# Master_MicroController_LED.net
KiCad netlist of a schematic drawn in Altium Designer
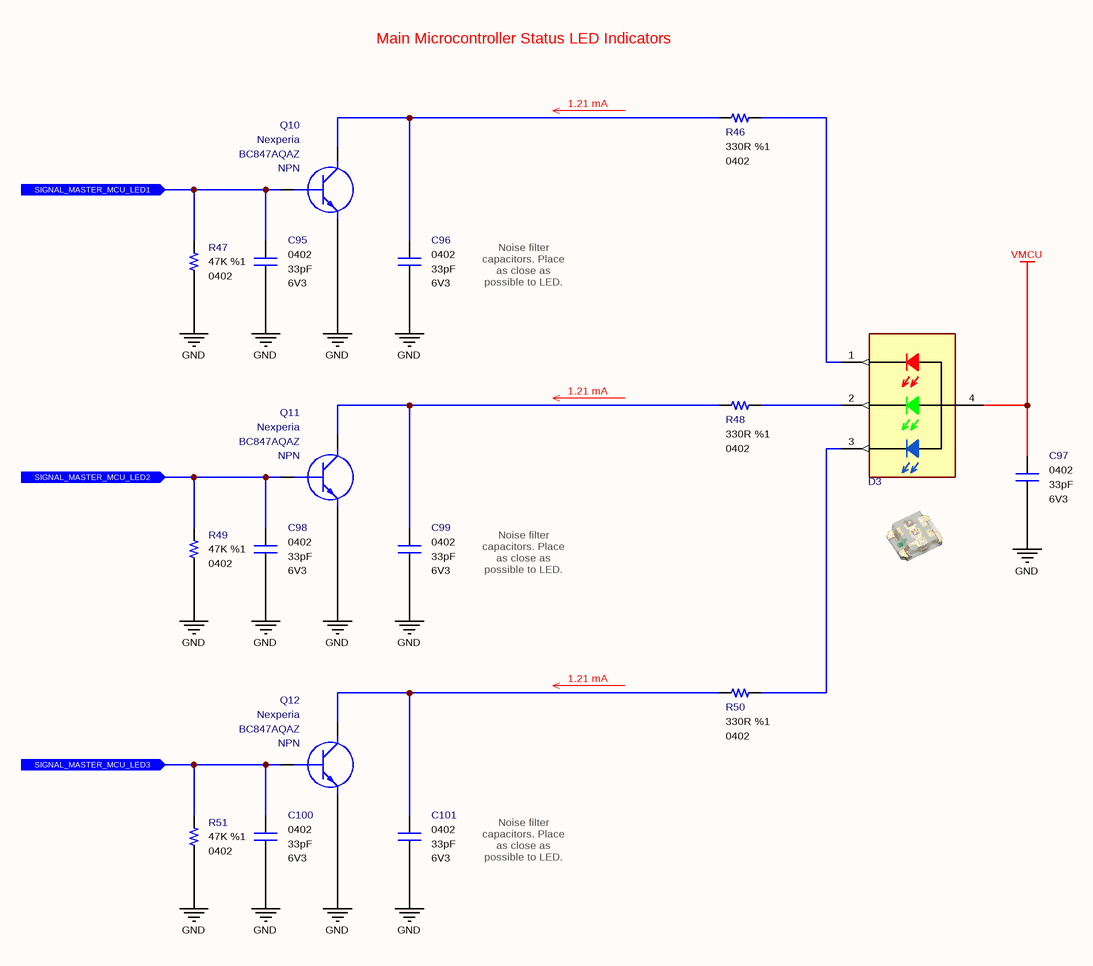
[diagram p0: Master MicroController LED.SchDoc]

(export (version "E")
  (design (tool "Eeschema 10.0.6"))
  (components
    (comp (ref "C95")
      (value "33pF")
      (footprint "CAPACITOR_0402")
      (description "Capacitor - 33pF [0402] (Ceramic)")
      (fields
        (field (name "CASE") "0402")
        (field (name "TOLERANCE") "10%")
        (field (name "VOLTAGE") "6V3")
        (field (name "MANUFACTURER PART NUMBER") "C0402C330J9RACAUTO")
      )
      (libsource (lib "Ovoo_Library") (part "Capacitor - 33pF [0402-6V3]"))
    )
    (comp (ref "C96")
      (value "33pF")
      (footprint "CAPACITOR_0402")
      (description "Capacitor - 33pF [0402] (Ceramic)")
      (fields
        (field (name "CASE") "0402")
        (field (name "TOLERANCE") "10%")
        (field (name "VOLTAGE") "6V3")
        (field (name "MANUFACTURER PART NUMBER") "C0402C330J9RACAUTO")
      )
      (libsource (lib "Ovoo_Library") (part "Capacitor - 33pF [0402-6V3]"))
    )
    (comp (ref "C97")
      (value "33pF")
      (footprint "CAPACITOR_0402")
      (description "Capacitor - 33pF [0402] (Ceramic)")
      (fields
        (field (name "CASE") "0402")
        (field (name "TOLERANCE") "10%")
        (field (name "VOLTAGE") "6V3")
        (field (name "MANUFACTURER PART NUMBER") "C0402C330J9RACAUTO")
      )
      (libsource (lib "Ovoo_Library") (part "Capacitor - 33pF [0402-6V3]"))
    )
    (comp (ref "C98")
      (value "33pF")
      (footprint "CAPACITOR_0402")
      (description "Capacitor - 33pF [0402] (Ceramic)")
      (fields
        (field (name "CASE") "0402")
        (field (name "TOLERANCE") "10%")
        (field (name "VOLTAGE") "6V3")
        (field (name "MANUFACTURER PART NUMBER") "C0402C330J9RACAUTO")
      )
      (libsource (lib "Ovoo_Library") (part "Capacitor - 33pF [0402-6V3]"))
    )
    (comp (ref "C99")
      (value "33pF")
      (footprint "CAPACITOR_0402")
      (description "Capacitor - 33pF [0402] (Ceramic)")
      (fields
        (field (name "CASE") "0402")
        (field (name "TOLERANCE") "10%")
        (field (name "VOLTAGE") "6V3")
        (field (name "MANUFACTURER PART NUMBER") "C0402C330J9RACAUTO")
      )
      (libsource (lib "Ovoo_Library") (part "Capacitor - 33pF [0402-6V3]"))
    )
    (comp (ref "C100")
      (value "33pF")
      (footprint "CAPACITOR_0402")
      (description "Capacitor - 33pF [0402] (Ceramic)")
      (fields
        (field (name "CASE") "0402")
        (field (name "TOLERANCE") "10%")
        (field (name "VOLTAGE") "6V3")
        (field (name "MANUFACTURER PART NUMBER") "C0402C330J9RACAUTO")
      )
      (libsource (lib "Ovoo_Library") (part "Capacitor - 33pF [0402-6V3]"))
    )
    (comp (ref "C101")
      (value "33pF")
      (footprint "CAPACITOR_0402")
      (description "Capacitor - 33pF [0402] (Ceramic)")
      (fields
        (field (name "CASE") "0402")
        (field (name "TOLERANCE") "10%")
        (field (name "VOLTAGE") "6V3")
        (field (name "MANUFACTURER PART NUMBER") "C0402C330J9RACAUTO")
      )
      (libsource (lib "Ovoo_Library") (part "Capacitor - 33pF [0402-6V3]"))
    )
    (comp (ref "D3")
      (value "150066M153000")
      (footprint "Wurth_0606")
      (description "Standard LEDs - SMD PICOLED series Red LED")
      (fields (field (name "MOUSER PART NUMBER") "710-150066M153000"))
      (libsource (lib "Ovoo_Library") (part "Diode - RGB LED (150066M153000)"))
    )
    (comp (ref "Q10")
      (value "Bipolar NPN Transistors")
      (footprint "SOT1215")
      (description "Bipolar Transistors - BJT BC847AQA/DFN1010D-3/REEL 7\" Q2")
      (fields
        (field (name "MOUSER_PART_NUMBER") "771-BC847AQAZ")
        (field (name "MANUFACTURER_NAME") "Nexperia")
        (field (name "MANUFACTURER_PART_NUMBER") "BC847AQAZ")
        (field (name "POLARITY") "NPN")
      )
      (libsource (lib "Ovoo_Library") (part "Transistor - BC847"))
    )
    (comp (ref "Q11")
      (value "Bipolar NPN Transistors")
      (footprint "SOT1215")
      (description "Bipolar Transistors - BJT BC847AQA/DFN1010D-3/REEL 7\" Q2")
      (fields
        (field (name "MOUSER_PART_NUMBER") "771-BC847AQAZ")
        (field (name "MANUFACTURER_NAME") "Nexperia")
        (field (name "MANUFACTURER_PART_NUMBER") "BC847AQAZ")
        (field (name "POLARITY") "NPN")
      )
      (libsource (lib "Ovoo_Library") (part "Transistor - BC847"))
    )
    (comp (ref "Q12")
      (value "Bipolar NPN Transistors")
      (footprint "SOT1215")
      (description "Bipolar Transistors - BJT BC847AQA/DFN1010D-3/REEL 7\" Q2")
      (fields
        (field (name "MOUSER_PART_NUMBER") "771-BC847AQAZ")
        (field (name "MANUFACTURER_NAME") "Nexperia")
        (field (name "MANUFACTURER_PART_NUMBER") "BC847AQAZ")
        (field (name "POLARITY") "NPN")
      )
      (libsource (lib "Ovoo_Library") (part "Transistor - BC847"))
    )
    (comp (ref "R46")
      (value "330R")
      (footprint "RESISTOR_0402")
      (description "Thick Film Resistors - SMD 1/16 W 330 Ohm 1%")
      (fields
        (field (name "TOLERANCE") "%1")
        (field (name "CASE") "0402")
        (field (name "MANUFACTURER PART NUMBER") "CRCW0402330RFKED")
        (field (name "MOUSER PART NUMBER") "71-CRCW0402-330-E3")
      )
      (libsource (lib "Ovoo_Library") (part "Resistor - 330R"))
    )
    (comp (ref "R47")
      (value "47K")
      (footprint "RESISTOR_0402")
      (description "Thick Film Resistors - SMD 1/16 W 47 Kohms 1%")
      (fields
        (field (name "TOLERANCE") "%1")
        (field (name "CASE") "0402")
        (field (name "MANUFACTURER PART NUMBER") "CRCW040247K0FKED")
        (field (name "MOUSER PART NUMBER") "71-CRCW0402-47K-E3")
      )
      (libsource (lib "Ovoo_Library") (part "Resistor - 47K"))
    )
    (comp (ref "R48")
      (value "330R")
      (footprint "RESISTOR_0402")
      (description "Thick Film Resistors - SMD 1/16 W 330 Ohm 1%")
      (fields
        (field (name "TOLERANCE") "%1")
        (field (name "CASE") "0402")
        (field (name "MANUFACTURER PART NUMBER") "CRCW0402330RFKED")
        (field (name "MOUSER PART NUMBER") "71-CRCW0402-330-E3")
      )
      (libsource (lib "Ovoo_Library") (part "Resistor - 330R"))
    )
    (comp (ref "R49")
      (value "47K")
      (footprint "RESISTOR_0402")
      (description "Thick Film Resistors - SMD 1/16 W 47 Kohms 1%")
      (fields
        (field (name "TOLERANCE") "%1")
        (field (name "CASE") "0402")
        (field (name "MANUFACTURER PART NUMBER") "CRCW040247K0FKED")
        (field (name "MOUSER PART NUMBER") "71-CRCW0402-47K-E3")
      )
      (libsource (lib "Ovoo_Library") (part "Resistor - 47K"))
    )
    (comp (ref "R50")
      (value "330R")
      (footprint "RESISTOR_0402")
      (description "Thick Film Resistors - SMD 1/16 W 330 Ohm 1%")
      (fields
        (field (name "TOLERANCE") "%1")
        (field (name "CASE") "0402")
        (field (name "MANUFACTURER PART NUMBER") "CRCW0402330RFKED")
        (field (name "MOUSER PART NUMBER") "71-CRCW0402-330-E3")
      )
      (libsource (lib "Ovoo_Library") (part "Resistor - 330R"))
    )
    (comp (ref "R51")
      (value "47K")
      (footprint "RESISTOR_0402")
      (description "Thick Film Resistors - SMD 1/16 W 47 Kohms 1%")
      (fields
        (field (name "TOLERANCE") "%1")
        (field (name "CASE") "0402")
        (field (name "MANUFACTURER PART NUMBER") "CRCW040247K0FKED")
        (field (name "MOUSER PART NUMBER") "71-CRCW0402-47K-E3")
      )
      (libsource (lib "Ovoo_Library") (part "Resistor - 47K"))
    )
  )
  (nets
    (net (code "1") (name "/SIGNAL_MASTER_MCU_LED1") (class "Default")
      (node (ref "C95") (pin "1") (pinfunction "1_1") (pintype "passive"))
      (node (ref "Q10") (pin "1") (pinfunction "B_1") (pintype "passive"))
      (node (ref "R47") (pin "2") (pinfunction "2_2") (pintype "passive"))
    )
    (net (code "2") (name "/SIGNAL_MASTER_MCU_LED2") (class "Default")
      (node (ref "C98") (pin "1") (pinfunction "1_1") (pintype "passive"))
      (node (ref "Q11") (pin "1") (pinfunction "B_1") (pintype "passive"))
      (node (ref "R49") (pin "2") (pinfunction "2_2") (pintype "passive"))
    )
    (net (code "3") (name "/SIGNAL_MASTER_MCU_LED3") (class "Default")
      (node (ref "C100") (pin "1") (pinfunction "1_1") (pintype "passive"))
      (node (ref "Q12") (pin "1") (pinfunction "B_1") (pintype "passive"))
      (node (ref "R51") (pin "2") (pinfunction "2_2") (pintype "passive"))
    )
    (net (code "4") (name "GND") (class "Default")
      (node (ref "C100") (pin "2") (pinfunction "2_2") (pintype "passive"))
      (node (ref "C101") (pin "2") (pinfunction "2_2") (pintype "passive"))
      (node (ref "C95") (pin "2") (pinfunction "2_2") (pintype "passive"))
      (node (ref "C96") (pin "2") (pinfunction "2_2") (pintype "passive"))
      (node (ref "C97") (pin "2") (pinfunction "2_2") (pintype "passive"))
      (node (ref "C98") (pin "2") (pinfunction "2_2") (pintype "passive"))
      (node (ref "C99") (pin "2") (pinfunction "2_2") (pintype "passive"))
      (node (ref "Q10") (pin "2") (pinfunction "E_2") (pintype "passive"))
      (node (ref "Q11") (pin "2") (pinfunction "E_2") (pintype "passive"))
      (node (ref "Q12") (pin "2") (pinfunction "E_2") (pintype "passive"))
      (node (ref "R47") (pin "1") (pinfunction "1_1") (pintype "passive"))
      (node (ref "R49") (pin "1") (pinfunction "1_1") (pintype "passive"))
      (node (ref "R51") (pin "1") (pinfunction "1_1") (pintype "passive"))
    )
    (net (code "5") (name "Net-(D3-Pad1)") (class "Default")
      (node (ref "D3") (pin "1") (pinfunction "1_1") (pintype "output"))
      (node (ref "R46") (pin "2") (pinfunction "2_2") (pintype "passive"))
    )
    (net (code "6") (name "Net-(D3-Pad2)") (class "Default")
      (node (ref "D3") (pin "2") (pinfunction "2_2") (pintype "output"))
      (node (ref "R48") (pin "2") (pinfunction "2_2") (pintype "passive"))
    )
    (net (code "7") (name "Net-(D3-Pad3)") (class "Default")
      (node (ref "D3") (pin "3") (pinfunction "3_3") (pintype "output"))
      (node (ref "R50") (pin "2") (pinfunction "2_2") (pintype "passive"))
    )
    (net (code "8") (name "Net-(Q10-C)") (class "Default")
      (node (ref "C96") (pin "1") (pinfunction "1_1") (pintype "passive"))
      (node (ref "Q10") (pin "3") (pinfunction "C_3") (pintype "passive"))
      (node (ref "R46") (pin "1") (pinfunction "1_1") (pintype "passive"))
    )
    (net (code "9") (name "Net-(Q11-C)") (class "Default")
      (node (ref "C99") (pin "1") (pinfunction "1_1") (pintype "passive"))
      (node (ref "Q11") (pin "3") (pinfunction "C_3") (pintype "passive"))
      (node (ref "R48") (pin "1") (pinfunction "1_1") (pintype "passive"))
    )
    (net (code "10") (name "Net-(Q12-C)") (class "Default")
      (node (ref "C101") (pin "1") (pinfunction "1_1") (pintype "passive"))
      (node (ref "Q12") (pin "3") (pinfunction "C_3") (pintype "passive"))
      (node (ref "R50") (pin "1") (pinfunction "1_1") (pintype "passive"))
    )
    (net (code "11") (name "VMCU") (class "Default")
      (node (ref "C97") (pin "1") (pinfunction "1_1") (pintype "passive"))
      (node (ref "D3") (pin "4") (pinfunction "4_4") (pintype "power_in"))
    )
  )
)
